# MTB-v1_2_0.net
KiCad netlist of a schematic drawn in EAGLE
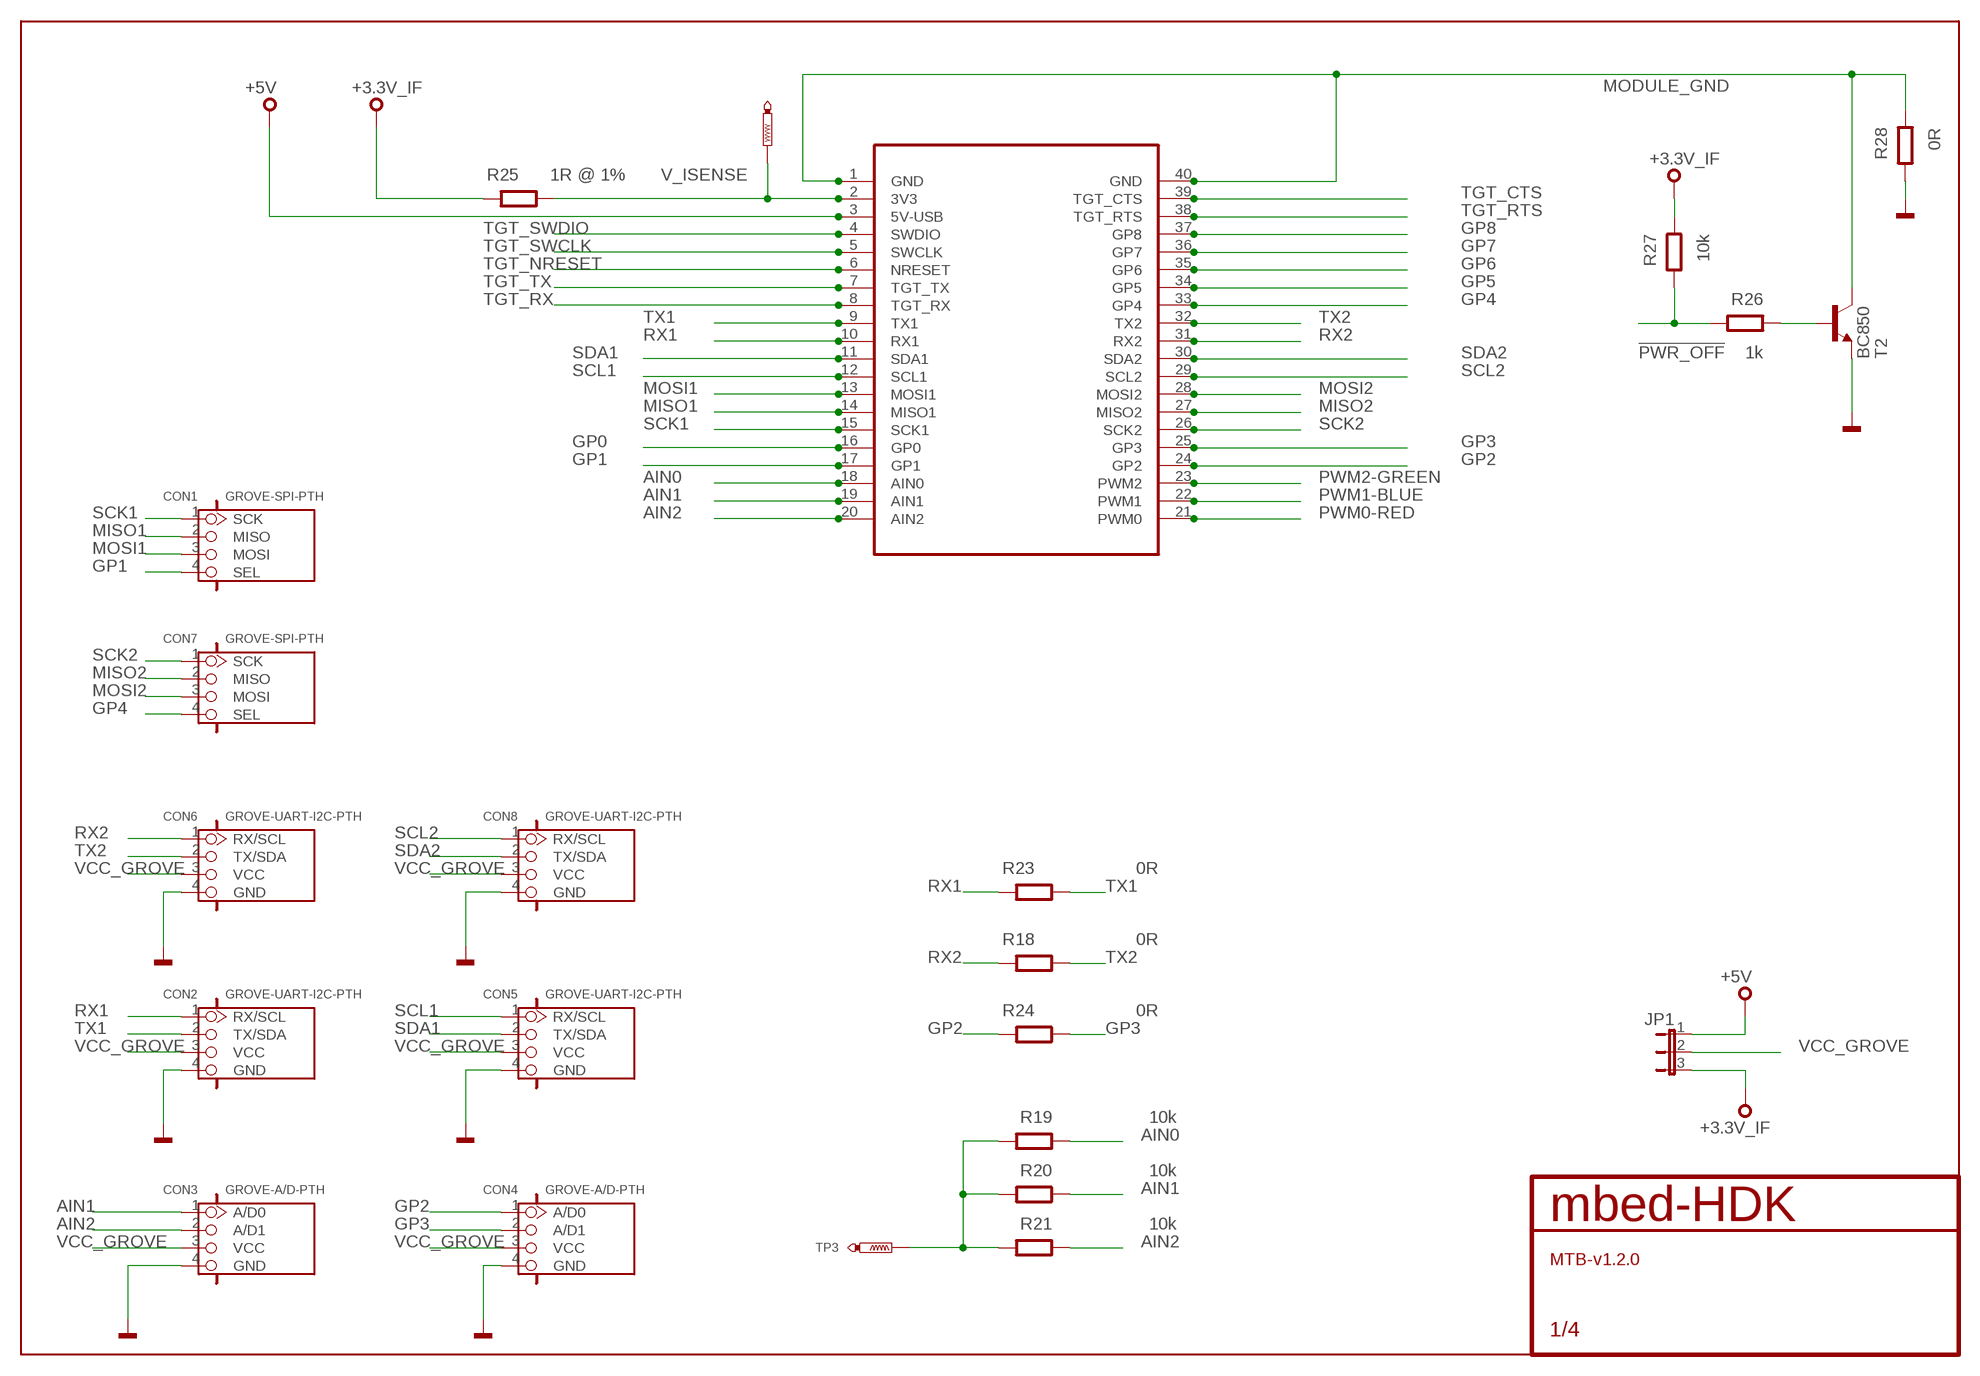
[diagram p0: schematic, sheet 1]
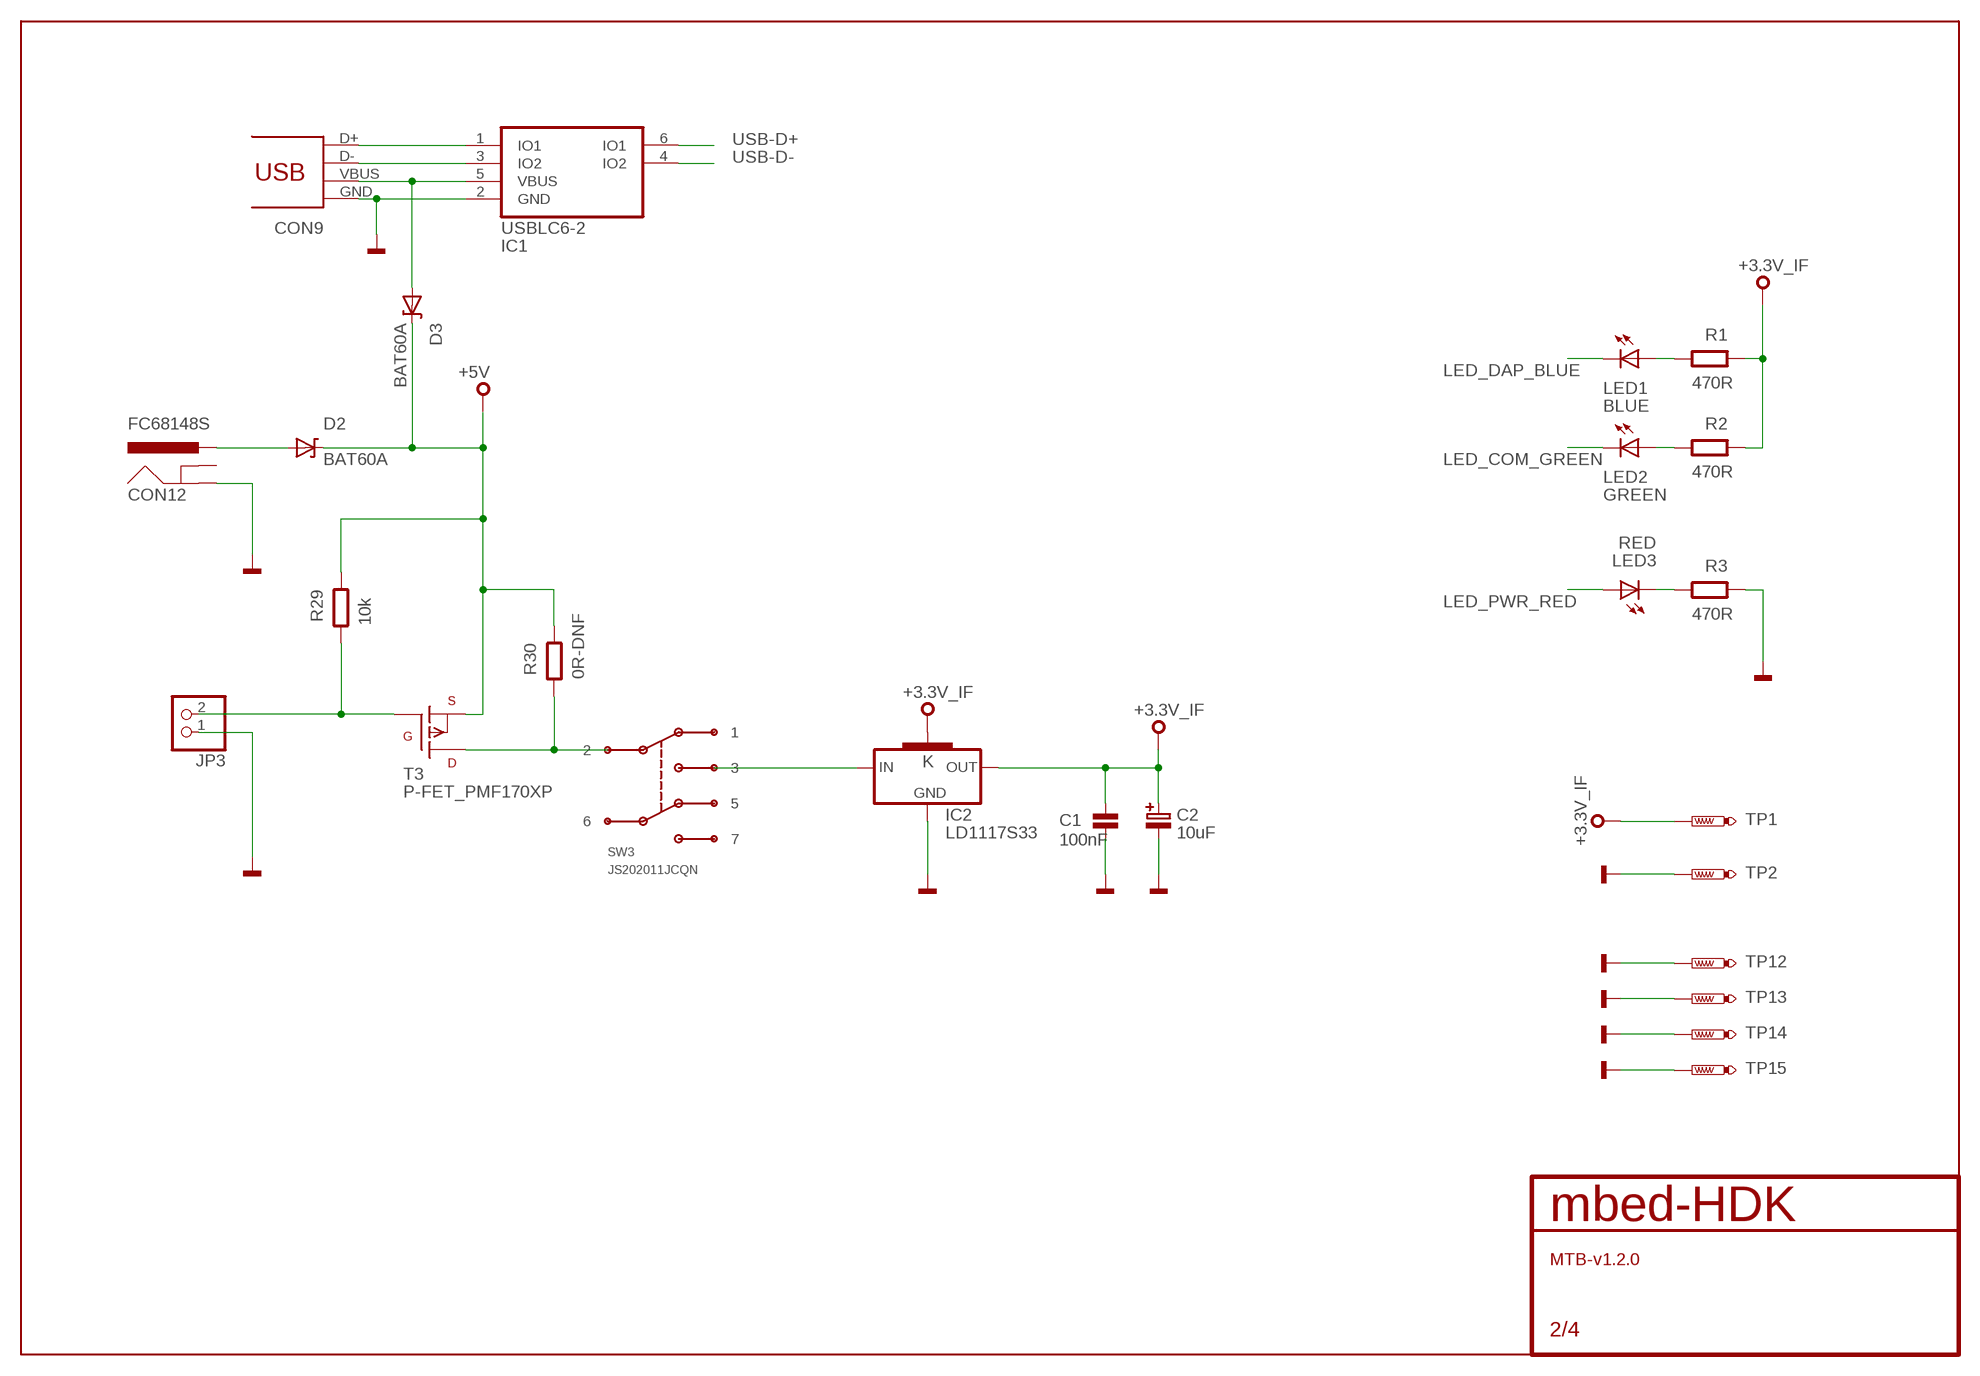
[diagram p1: schematic, sheet 2]
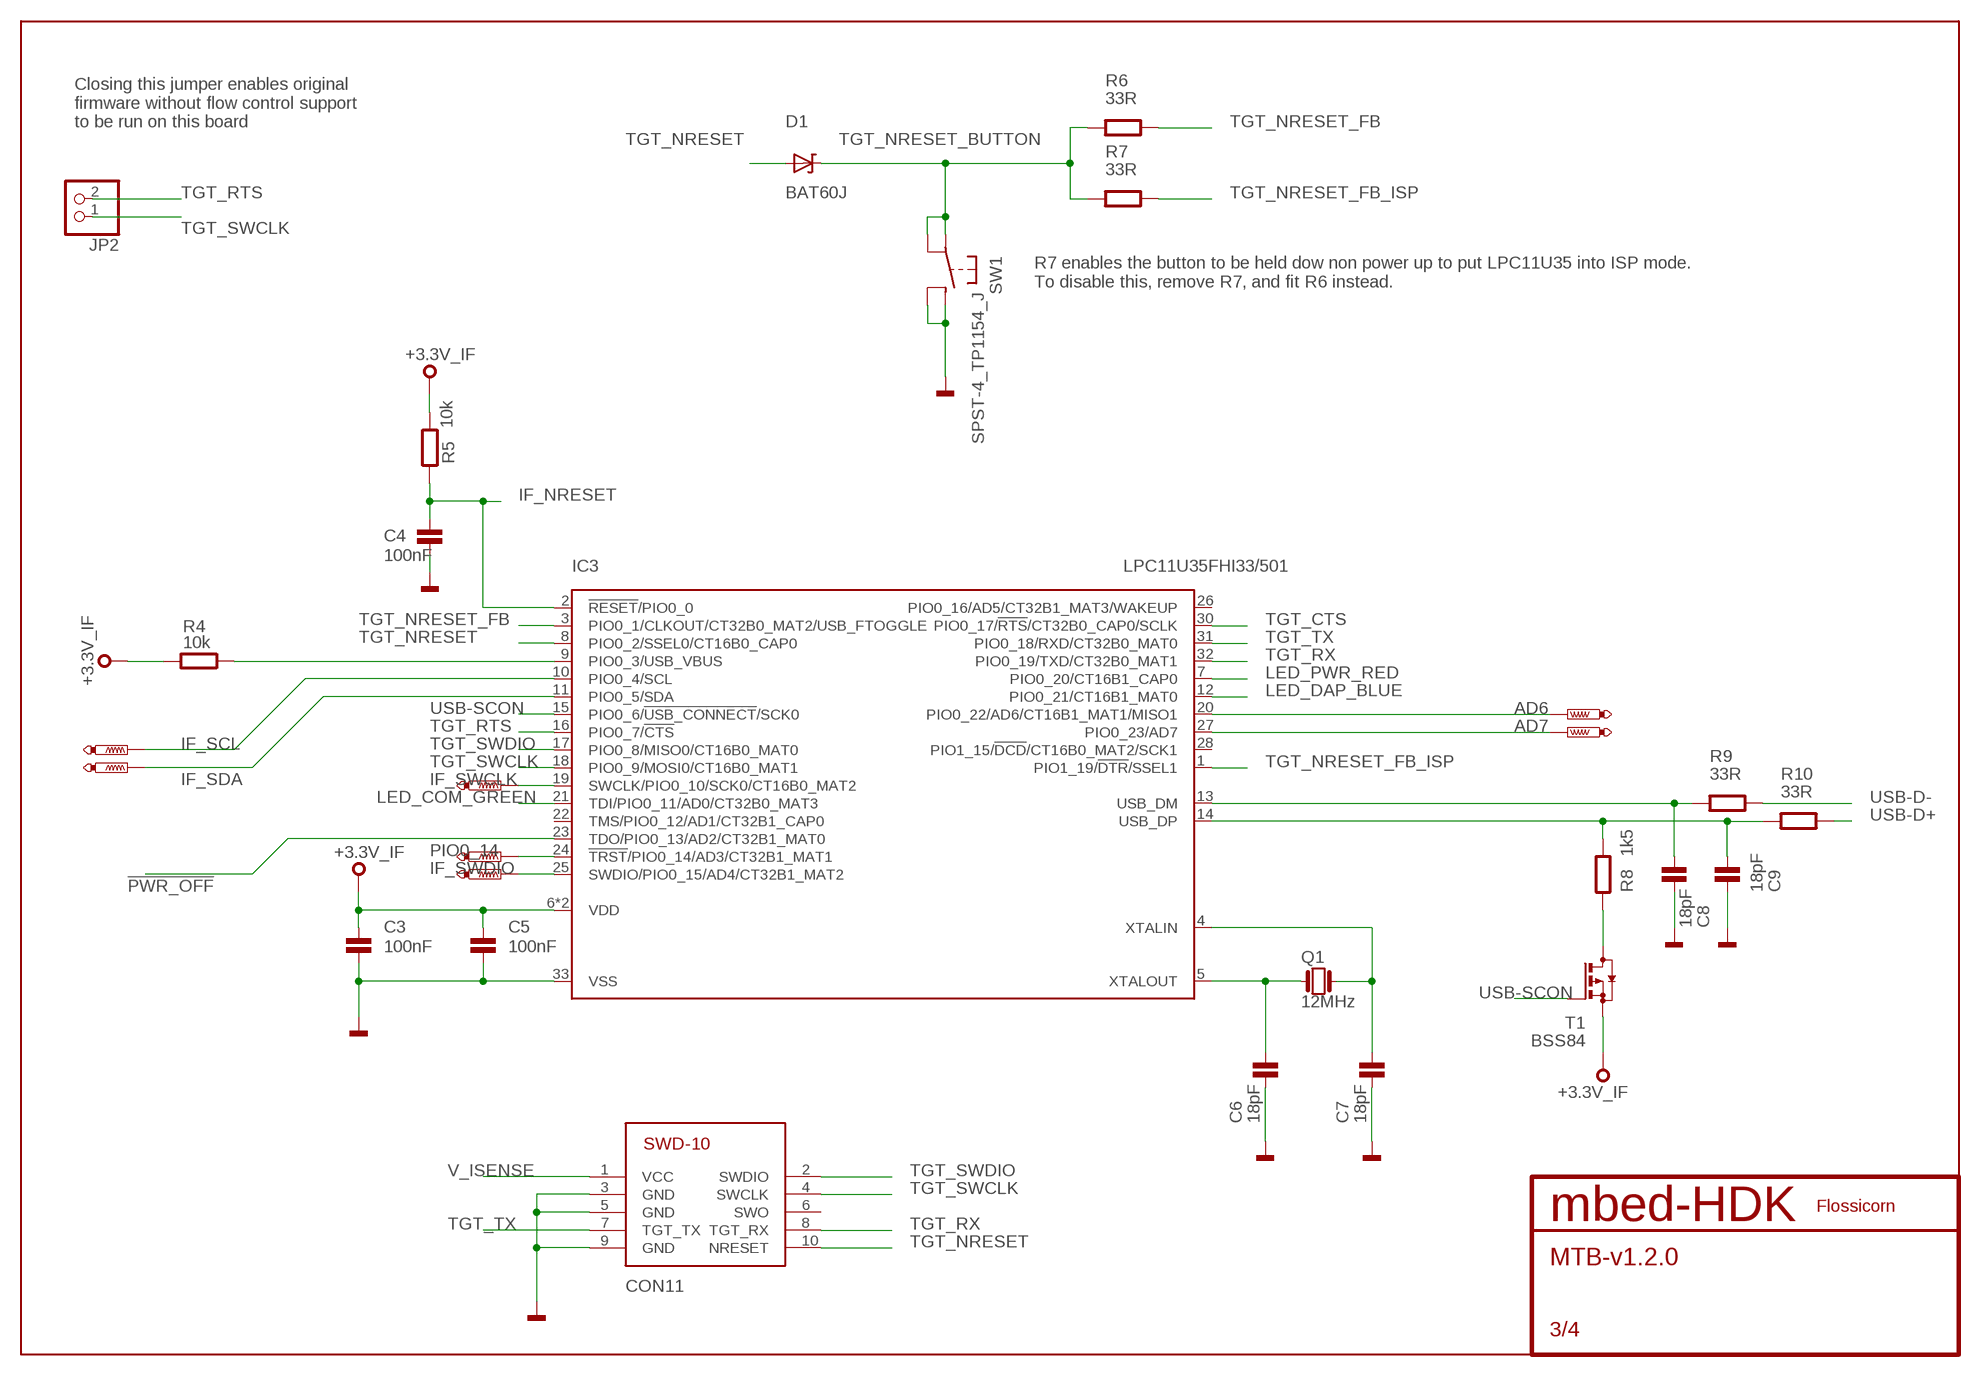
[diagram p2: schematic, sheet 3]
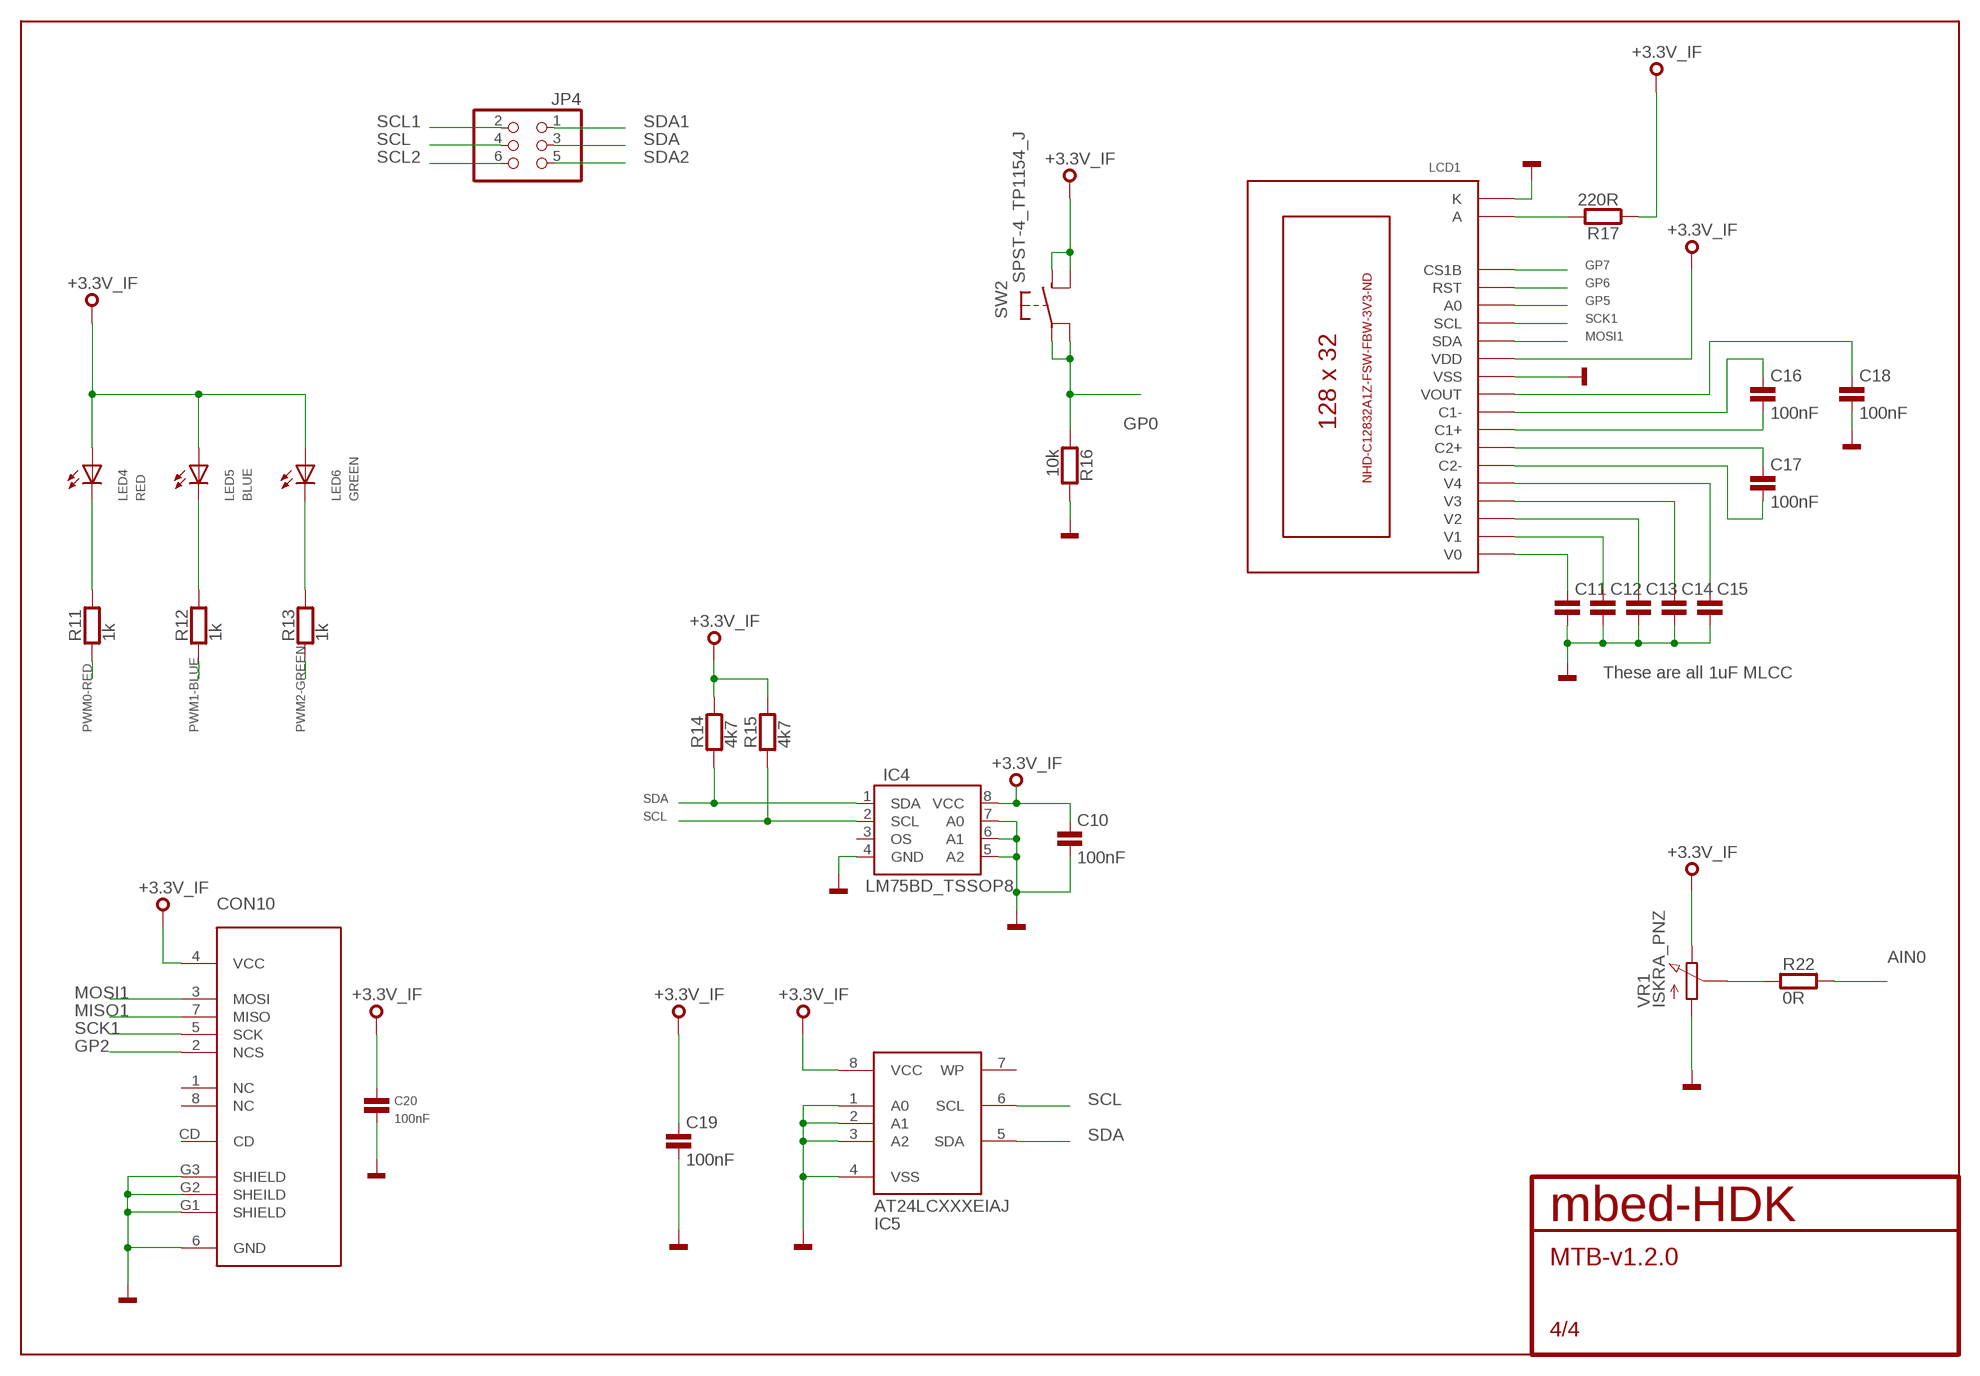
[diagram p3: schematic, sheet 4]

(export (version "E")
  (design (tool "Eeschema 10.0.6"))
  (components
    (comp (ref "C10")
      (value "100nF")
      (footprint "eagle-import:0603")
      (libsource (lib "eagle-import") (part "mbed-rlcq_C0603"))
    )
    (comp (ref "C11")
      (value "100nF")
      (footprint "eagle-import:0603")
      (libsource (lib "eagle-import") (part "mbed-rlcq_C0603"))
    )
    (comp (ref "C12")
      (value "100nF")
      (footprint "eagle-import:0603")
      (libsource (lib "eagle-import") (part "mbed-rlcq_C0603"))
    )
    (comp (ref "C13")
      (value "100nF")
      (footprint "eagle-import:0603")
      (libsource (lib "eagle-import") (part "mbed-rlcq_C0603"))
    )
    (comp (ref "C14")
      (value "100nF")
      (footprint "eagle-import:0603")
      (libsource (lib "eagle-import") (part "mbed-rlcq_C0603"))
    )
    (comp (ref "C15")
      (value "100nF")
      (footprint "eagle-import:0603")
      (libsource (lib "eagle-import") (part "mbed-rlcq_C0603"))
    )
    (comp (ref "C16")
      (value "100nF")
      (footprint "eagle-import:0603")
      (libsource (lib "eagle-import") (part "mbed-rlcq_C0603"))
    )
    (comp (ref "C17")
      (value "100nF")
      (footprint "eagle-import:0603")
      (libsource (lib "eagle-import") (part "mbed-rlcq_C0603"))
    )
    (comp (ref "C18")
      (value "100nF")
      (footprint "eagle-import:0603")
      (libsource (lib "eagle-import") (part "mbed-rlcq_C0603"))
    )
    (comp (ref "C19")
      (value "100nF")
      (footprint "eagle-import:0603")
      (libsource (lib "eagle-import") (part "mbed-rlcq_C0603"))
    )
    (comp (ref "C20")
      (value "100nF")
      (footprint "eagle-import:0603")
      (libsource (lib "eagle-import") (part "C0603"))
    )
    (comp (ref "CON10")
      (value "MICRO-SD")
      (footprint "eagle-import:AMPHENOL-101-00660-68-6")
      (libsource (lib "eagle-import") (part "MICRO-SD"))
    )
    (comp (ref "IC4")
      (value "LM75BD_TSSOP8")
      (footprint "eagle-import:TSSOP8")
      (libsource (lib "eagle-import") (part "LM75BD_TSSOP8"))
    )
    (comp (ref "IC5")
      (value "AT24LCXXXEIAJ")
      (footprint "eagle-import:SO08-EIAJ")
      (libsource (lib "eagle-import") (part "AT24LCXXXEIAJ"))
    )
    (comp (ref "JP4")
      (value "PINHD-2X3")
      (footprint "eagle-import:2X03")
      (libsource (lib "eagle-import") (part "PINHD-2X3"))
    )
    (comp (ref "LCD1")
      (value "C12832A1Z")
      (footprint "eagle-import:C12832A1Z")
      (libsource (lib "eagle-import") (part "C12832A1Z"))
    )
    (comp (ref "LED4")
      (value "RED")
      (footprint "eagle-import:CHIPLED_0603")
      (libsource (lib "eagle-import") (part "LED0603"))
    )
    (comp (ref "LED5")
      (value "BLUE")
      (footprint "eagle-import:CHIPLED_0603")
      (libsource (lib "eagle-import") (part "LED0603"))
    )
    (comp (ref "LED6")
      (value "GREEN")
      (footprint "eagle-import:CHIPLED_0603")
      (libsource (lib "eagle-import") (part "LED0603"))
    )
    (comp (ref "R11")
      (value "1k")
      (footprint "eagle-import:0603")
      (libsource (lib "eagle-import") (part "mbed-rlcq_R0603"))
    )
    (comp (ref "R12")
      (value "1k")
      (footprint "eagle-import:0603")
      (libsource (lib "eagle-import") (part "mbed-rlcq_R0603"))
    )
    (comp (ref "R13")
      (value "1k")
      (footprint "eagle-import:0603")
      (libsource (lib "eagle-import") (part "mbed-rlcq_R0603"))
    )
    (comp (ref "R14")
      (value "4k7")
      (footprint "eagle-import:0603")
      (libsource (lib "eagle-import") (part "mbed-rlcq_R0603"))
    )
    (comp (ref "R15")
      (value "4k7")
      (footprint "eagle-import:0603")
      (libsource (lib "eagle-import") (part "mbed-rlcq_R0603"))
    )
    (comp (ref "R16")
      (value "10k")
      (footprint "eagle-import:0603")
      (libsource (lib "eagle-import") (part "mbed-rlcq_R0603"))
    )
    (comp (ref "R17")
      (value "220R")
      (footprint "eagle-import:0603")
      (libsource (lib "eagle-import") (part "mbed-rlcq_R0603"))
    )
    (comp (ref "R22")
      (value "0R")
      (footprint "eagle-import:0603")
      (libsource (lib "eagle-import") (part "mbed-rlcq_R0603"))
    )
    (comp (ref "SW2")
      (value "SPST-4_TP1154_J")
      (footprint "eagle-import:TP-1154X")
      (libsource (lib "eagle-import") (part "SPST-4_TP1154_J"))
    )
    (comp (ref "VR1")
      (value "ISKRA_PNZ")
      (footprint "eagle-import:CA14V")
      (libsource (lib "eagle-import") (part "ISKRA_PNZ"))
    )
    (comp (ref "C1")
      (value "100nF")
      (footprint "eagle-import:0603")
      (libsource (lib "eagle-import") (part "C0603"))
    )
    (comp (ref "C2")
      (value "10uF")
      (footprint "eagle-import:SMC_B")
      (libsource (lib "eagle-import") (part "C-POLB"))
    )
    (comp (ref "CON9")
      (value "USB_MICROB")
      (footprint "eagle-import:MOLEX-47364-0001")
      (libsource (lib "eagle-import") (part "USB_MICROB"))
    )
    (comp (ref "CON12")
      (value "FC68148S")
      (footprint "eagle-import:FC68148S")
      (libsource (lib "eagle-import") (part "FC68148S"))
    )
    (comp (ref "D2")
      (value "BAT60A")
      (footprint "eagle-import:SOD323")
      (fields (field (name "MF") "Infineon"))
      (libsource (lib "eagle-import") (part "mbed-HDK-Transistor_BAT60A"))
    )
    (comp (ref "D3")
      (value "BAT60A")
      (footprint "eagle-import:SOD323")
      (fields (field (name "MF") "Infineon"))
      (libsource (lib "eagle-import") (part "mbed-HDK-Transistor_BAT60A"))
    )
    (comp (ref "IC1")
      (value "USBLC6-2SC6")
      (footprint "eagle-import:SOT23-6L")
      (libsource (lib "eagle-import") (part "USBLC6-2SC6"))
    )
    (comp (ref "IC2")
      (value "LD1117S33")
      (footprint "eagle-import:SOT223")
      (libsource (lib "eagle-import") (part "LD1117S33"))
    )
    (comp (ref "JP3")
      (value "PINHD-1X2")
      (footprint "eagle-import:1X02")
      (libsource (lib "eagle-import") (part "PINHD-1X2"))
    )
    (comp (ref "LED1")
      (value "BLUE")
      (footprint "eagle-import:CHIPLED_0603")
      (libsource (lib "eagle-import") (part "LED0603"))
    )
    (comp (ref "LED2")
      (value "GREEN")
      (footprint "eagle-import:CHIPLED_0603")
      (libsource (lib "eagle-import") (part "LED0603"))
    )
    (comp (ref "LED3")
      (value "RED")
      (footprint "eagle-import:CHIPLED_0603")
      (libsource (lib "eagle-import") (part "LED0603"))
    )
    (comp (ref "R1")
      (value "470R")
      (footprint "eagle-import:0603@1")
      (libsource (lib "eagle-import") (part "R0603"))
    )
    (comp (ref "R2")
      (value "470R")
      (footprint "eagle-import:0603@1")
      (libsource (lib "eagle-import") (part "R0603"))
    )
    (comp (ref "R3")
      (value "470R")
      (footprint "eagle-import:0603@1")
      (libsource (lib "eagle-import") (part "R0603"))
    )
    (comp (ref "R29")
      (value "10k")
      (footprint "eagle-import:0603@1")
      (libsource (lib "eagle-import") (part "R0603"))
    )
    (comp (ref "R30")
      (value "0R-DNF")
      (footprint "eagle-import:0603@1")
      (libsource (lib "eagle-import") (part "R0603"))
    )
    (comp (ref "SW3")
      (value "JS202011JCQN")
      (footprint "eagle-import:JS202011JCQN")
      (fields (field (name "MF") "C&K Components"))
      (libsource (lib "eagle-import") (part "JS202011JCQN"))
    )
    (comp (ref "T3")
      (value "P-FET_PMF170XP")
      (footprint "eagle-import:SOT23-BEC")
      (libsource (lib "eagle-import") (part "P-FET_PMF170XP"))
    )
    (comp (ref "TP1")
      (value "TEST-POINT-50R-PTH")
      (footprint "eagle-import:TP50-PTH")
      (libsource (lib "eagle-import") (part "TEST-POINT-50R-PTH"))
    )
    (comp (ref "TP2")
      (value "TEST-POINT-50R-PTH")
      (footprint "eagle-import:TP50-PTH")
      (libsource (lib "eagle-import") (part "TEST-POINT-50R-PTH"))
    )
    (comp (ref "TP12")
      (value "TEST-POINT-50R-PTH")
      (footprint "eagle-import:TP50-PTH")
      (libsource (lib "eagle-import") (part "TEST-POINT-50R-PTH"))
    )
    (comp (ref "TP13")
      (value "TEST-POINT-50R-PTH")
      (footprint "eagle-import:TP50-PTH")
      (libsource (lib "eagle-import") (part "TEST-POINT-50R-PTH"))
    )
    (comp (ref "TP14")
      (value "TEST-POINT-50R-PTH")
      (footprint "eagle-import:TP50-PTH")
      (libsource (lib "eagle-import") (part "TEST-POINT-50R-PTH"))
    )
    (comp (ref "TP15")
      (value "TEST-POINT-50R-PTH")
      (footprint "eagle-import:TP50-PTH")
      (libsource (lib "eagle-import") (part "TEST-POINT-50R-PTH"))
    )
    (comp (ref "CON1")
      (value "GROVE-SPI-PTH")
      (footprint "eagle-import:HW4-2.0")
      (libsource (lib "eagle-import") (part "GROVE-SPI-PTH"))
    )
    (comp (ref "CON2")
      (value "GROVE-UART-I2C-PTH")
      (footprint "eagle-import:HW4-2.0")
      (libsource (lib "eagle-import") (part "GROVE-UART-I2C-PTH"))
    )
    (comp (ref "CON3")
      (value "GROVE-A/D-PTH")
      (footprint "eagle-import:HW4-2.0")
      (libsource (lib "eagle-import") (part "GROVE-A/D-PTH"))
    )
    (comp (ref "CON4")
      (value "GROVE-A/D-PTH")
      (footprint "eagle-import:HW4-2.0")
      (libsource (lib "eagle-import") (part "GROVE-A/D-PTH"))
    )
    (comp (ref "CON5")
      (value "GROVE-UART-I2C-PTH")
      (footprint "eagle-import:HW4-2.0")
      (libsource (lib "eagle-import") (part "GROVE-UART-I2C-PTH"))
    )
    (comp (ref "CON6")
      (value "GROVE-UART-I2C-PTH")
      (footprint "eagle-import:HW4-2.0")
      (libsource (lib "eagle-import") (part "GROVE-UART-I2C-PTH"))
    )
    (comp (ref "CON7")
      (value "GROVE-SPI-PTH")
      (footprint "eagle-import:HW4-2.0")
      (libsource (lib "eagle-import") (part "GROVE-SPI-PTH"))
    )
    (comp (ref "CON8")
      (value "GROVE-UART-I2C-PTH")
      (footprint "eagle-import:HW4-2.0")
      (libsource (lib "eagle-import") (part "GROVE-UART-I2C-PTH"))
    )
    (comp (ref "JP1")
      (value "JP2E")
      (footprint "eagle-import:JP2")
      (libsource (lib "eagle-import") (part "JP2E"))
    )
    (comp (ref "R18")
      (value "0R")
      (footprint "eagle-import:0603@1")
      (libsource (lib "eagle-import") (part "R0603"))
    )
    (comp (ref "R19")
      (value "10k")
      (footprint "eagle-import:0603@1")
      (libsource (lib "eagle-import") (part "R0603"))
    )
    (comp (ref "R20")
      (value "10k")
      (footprint "eagle-import:0603@1")
      (libsource (lib "eagle-import") (part "R0603"))
    )
    (comp (ref "R21")
      (value "10k")
      (footprint "eagle-import:0603@1")
      (libsource (lib "eagle-import") (part "R0603"))
    )
    (comp (ref "R23")
      (value "0R")
      (footprint "eagle-import:0603@1")
      (libsource (lib "eagle-import") (part "R0603"))
    )
    (comp (ref "R24")
      (value "0R")
      (footprint "eagle-import:0603@1")
      (libsource (lib "eagle-import") (part "R0603"))
    )
    (comp (ref "R25")
      (value "1R @ 1%")
      (footprint "eagle-import:0603@1")
      (libsource (lib "eagle-import") (part "R0603"))
    )
    (comp (ref "R26")
      (value "1k")
      (footprint "eagle-import:0603@1")
      (libsource (lib "eagle-import") (part "R0603"))
    )
    (comp (ref "R27")
      (value "10k")
      (footprint "eagle-import:0603@1")
      (libsource (lib "eagle-import") (part "R0603"))
    )
    (comp (ref "R28")
      (value "0R")
      (footprint "eagle-import:0603@1")
      (libsource (lib "eagle-import") (part "R0603"))
    )
    (comp (ref "SKT1")
      (value "MODULE_SOCKET")
      (footprint "eagle-import:MODULE_SOCKET")
      (libsource (lib "eagle-import") (part "MODULE_SOCKET"))
    )
    (comp (ref "T2")
      (value "BC850")
      (footprint "eagle-import:SOT23")
      (libsource (lib "eagle-import") (part "BC850"))
    )
    (comp (ref "TP3")
      (value "TEST-POINT-50R-PTH")
      (footprint "eagle-import:TP50-PTH")
      (libsource (lib "eagle-import") (part "TEST-POINT-50R-PTH"))
    )
    (comp (ref "TP8")
      (value "PTR1TP07R")
      (footprint "eagle-import:TP07R")
      (libsource (lib "eagle-import") (part "PTR1TP07R"))
    )
    (comp (ref "C3")
      (value "100nF")
      (footprint "eagle-import:0603")
      (libsource (lib "eagle-import") (part "C0603"))
    )
    (comp (ref "C4")
      (value "100nF")
      (footprint "eagle-import:0603")
      (libsource (lib "eagle-import") (part "C0603"))
    )
    (comp (ref "C5")
      (value "100nF")
      (footprint "eagle-import:0603")
      (libsource (lib "eagle-import") (part "C0603"))
    )
    (comp (ref "C6")
      (value "18pF")
      (footprint "eagle-import:0603")
      (libsource (lib "eagle-import") (part "C0603"))
    )
    (comp (ref "C7")
      (value "18pF")
      (footprint "eagle-import:0603")
      (libsource (lib "eagle-import") (part "C0603"))
    )
    (comp (ref "C8")
      (value "18pF")
      (footprint "eagle-import:0603")
      (libsource (lib "eagle-import") (part "C0603"))
    )
    (comp (ref "C9")
      (value "18pF")
      (footprint "eagle-import:0603")
      (libsource (lib "eagle-import") (part "C0603"))
    )
    (comp (ref "CON11")
      (value "SWD-10/TC2050_SMD")
      (footprint "eagle-import:FTSH-105-02")
      (libsource (lib "eagle-import") (part "SWD-10/TC2050_SMD"))
    )
    (comp (ref "D1")
      (value "BAT60J")
      (footprint "eagle-import:BAT60A")
      (libsource (lib "eagle-import") (part "BAT60A"))
    )
    (comp (ref "IC3")
      (value "LPC11U35FHI33/501")
      (footprint "eagle-import:SOT617-3")
      (libsource (lib "eagle-import") (part "LPC11U35FHI33/501"))
    )
    (comp (ref "JP2")
      (value "PINHD-1X2")
      (footprint "eagle-import:1X02")
      (libsource (lib "eagle-import") (part "PINHD-1X2"))
    )
    (comp (ref "Q1")
      (value "12MHz")
      (footprint "eagle-import:3.2X.2.5")
      (libsource (lib "eagle-import") (part "Q_3.2X2.5"))
    )
    (comp (ref "R4")
      (value "10k")
      (footprint "eagle-import:0603@1")
      (libsource (lib "eagle-import") (part "R0603"))
    )
    (comp (ref "R5")
      (value "10k")
      (footprint "eagle-import:0603@1")
      (libsource (lib "eagle-import") (part "R0603"))
    )
    (comp (ref "R6")
      (value "33R")
      (footprint "eagle-import:0603@1")
      (libsource (lib "eagle-import") (part "R0603"))
    )
    (comp (ref "R7")
      (value "33R")
      (footprint "eagle-import:0603@1")
      (libsource (lib "eagle-import") (part "R0603"))
    )
    (comp (ref "R8")
      (value "1k5")
      (footprint "eagle-import:0603@1")
      (libsource (lib "eagle-import") (part "R0603"))
    )
    (comp (ref "R9")
      (value "33R")
      (footprint "eagle-import:0603@1")
      (libsource (lib "eagle-import") (part "R0603"))
    )
    (comp (ref "R10")
      (value "33R")
      (footprint "eagle-import:0603@1")
      (libsource (lib "eagle-import") (part "R0603"))
    )
    (comp (ref "SS1")
      (value "FLOSSICORN0.5")
      (footprint "eagle-import:FLOSSICORN-0.5")
      (libsource (lib "eagle-import") (part "FLOSSICORN0.5"))
    )
    (comp (ref "SW1")
      (value "SPST-4_TP1154_J")
      (footprint "eagle-import:TP-1154X")
      (libsource (lib "eagle-import") (part "SPST-4_TP1154_J"))
    )
    (comp (ref "T1")
      (value "BSS84")
      (footprint "eagle-import:SOT23")
      (libsource (lib "eagle-import") (part "BSS84"))
    )
    (comp (ref "TP4")
      (value "PTR1TP07R")
      (footprint "eagle-import:TP07R")
      (libsource (lib "eagle-import") (part "PTR1TP07R"))
    )
    (comp (ref "TP5")
      (value "PTR1TP07R")
      (footprint "eagle-import:TP07R")
      (libsource (lib "eagle-import") (part "PTR1TP07R"))
    )
    (comp (ref "TP6")
      (value "PTR1TP07R")
      (footprint "eagle-import:TP07R")
      (libsource (lib "eagle-import") (part "PTR1TP07R"))
    )
    (comp (ref "TP7")
      (value "PTR1TP07R")
      (footprint "eagle-import:TP07R")
      (libsource (lib "eagle-import") (part "PTR1TP07R"))
    )
    (comp (ref "TP9")
      (value "PTR1TP07R")
      (footprint "eagle-import:TP07R")
      (libsource (lib "eagle-import") (part "PTR1TP07R"))
    )
    (comp (ref "TP10")
      (value "PTR1TP07R")
      (footprint "eagle-import:TP07R")
      (libsource (lib "eagle-import") (part "PTR1TP07R"))
    )
    (comp (ref "TP11")
      (value "PTR1TP07R")
      (footprint "eagle-import:TP07R")
      (libsource (lib "eagle-import") (part "PTR1TP07R"))
    )
  )
  (nets
    (net (code "1") (name "+3.3V_IF") (class "Default")
      (node (ref "C1") (pin "1") (pinfunction "P$1_1") (pintype "passive"))
      (node (ref "C10") (pin "1") (pinfunction "P$1_1") (pintype "passive"))
      (node (ref "C19") (pin "1") (pinfunction "P$1_1") (pintype "passive"))
      (node (ref "C2") (pin "+") (pinfunction "+_+") (pintype "passive"))
      (node (ref "C20") (pin "1") (pinfunction "P$1_1") (pintype "passive"))
      (node (ref "C3") (pin "1") (pinfunction "P$1_1") (pintype "passive"))
      (node (ref "C5") (pin "1") (pinfunction "P$1_1") (pintype "passive"))
      (node (ref "CON10") (pin "4") (pinfunction "VCC_4") (pintype "bidirectional"))
      (node (ref "IC2") (pin "2") (pinfunction "OUT_2") (pintype "passive"))
      (node (ref "IC2") (pin "4") (pinfunction "K_4") (pintype "passive"))
      (node (ref "IC3") (pin "29") (pinfunction "VDD_29") (pintype "passive"))
      (node (ref "IC3") (pin "6") (pinfunction "VDD_6") (pintype "passive"))
      (node (ref "IC4") (pin "8") (pinfunction "VCC_8") (pintype "bidirectional"))
      (node (ref "IC5") (pin "8") (pinfunction "VCC_8") (pintype "power_in"))
      (node (ref "JP1") (pin "3") (pinfunction "3_3") (pintype "passive"))
      (node (ref "LCD1") (pin "P$12") (pinfunction "VDD_P$12") (pintype "bidirectional"))
      (node (ref "LED4") (pin "A") (pinfunction "A_A") (pintype "passive"))
      (node (ref "LED5") (pin "A") (pinfunction "A_A") (pintype "passive"))
      (node (ref "LED6") (pin "A") (pinfunction "A_A") (pintype "passive"))
      (node (ref "R1") (pin "1") (pinfunction "P$1_1") (pintype "passive"))
      (node (ref "R14") (pin "2") (pinfunction "P$2_2") (pintype "passive"))
      (node (ref "R15") (pin "2") (pinfunction "P$2_2") (pintype "passive"))
      (node (ref "R17") (pin "1") (pinfunction "P$1_1") (pintype "passive"))
      (node (ref "R2") (pin "1") (pinfunction "P$1_1") (pintype "passive"))
      (node (ref "R25") (pin "2") (pinfunction "P$2_2") (pintype "passive"))
      (node (ref "R27") (pin "1") (pinfunction "P$1_1") (pintype "passive"))
      (node (ref "R4") (pin "2") (pinfunction "P$2_2") (pintype "passive"))
      (node (ref "R5") (pin "2") (pinfunction "P$2_2") (pintype "passive"))
      (node (ref "SW2") (pin "B1") (pinfunction "B1_B1") (pintype "passive"))
      (node (ref "SW2") (pin "B2") (pinfunction "B2_B2") (pintype "passive"))
      (node (ref "T1") (pin "2") (pinfunction "S_2") (pintype "passive"))
      (node (ref "TP1") (pin "TP") (pinfunction "TP_TP") (pintype "input"))
      (node (ref "VR1") (pin "P$3") (pinfunction "E_P$3") (pintype "passive"))
    )
    (net (code "2") (name "+5V") (class "Default")
      (node (ref "D2") (pin "K") (pinfunction "K_K") (pintype "passive"))
      (node (ref "D3") (pin "K") (pinfunction "K_K") (pintype "passive"))
      (node (ref "JP1") (pin "1") (pinfunction "1_1") (pintype "passive"))
      (node (ref "R29") (pin "1") (pinfunction "P$1_1") (pintype "passive"))
      (node (ref "R30") (pin "1") (pinfunction "P$1_1") (pintype "passive"))
      (node (ref "SKT1") (pin "3") (pinfunction "5V-USB_3") (pintype "bidirectional"))
      (node (ref "SKT1") (pin "P$43") (pinfunction "P$43_P$43") (pintype "bidirectional"))
      (node (ref "T3") (pin "E") (pinfunction "S_E") (pintype "passive"))
    )
    (net (code "3") (name "AD6") (class "Default")
      (node (ref "IC3") (pin "20") (pinfunction "PIO0_22/AD6/CT16B1_MAT1/MISO1_20") (pintype "bidirectional"))
      (node (ref "TP7") (pin "TP") (pinfunction "TP_TP") (pintype "input"))
    )
    (net (code "4") (name "AD7") (class "Default")
      (node (ref "IC3") (pin "27") (pinfunction "PIO0_23/AD7_27") (pintype "bidirectional"))
      (node (ref "TP6") (pin "TP") (pinfunction "TP_TP") (pintype "input"))
    )
    (net (code "5") (name "AIN0") (class "Default")
      (node (ref "R19") (pin "1") (pinfunction "P$1_1") (pintype "passive"))
      (node (ref "R22") (pin "2") (pinfunction "P$2_2") (pintype "passive"))
      (node (ref "SKT1") (pin "18") (pinfunction "AIN0_18") (pintype "bidirectional"))
      (node (ref "SKT1") (pin "P$58") (pinfunction "P$58_P$58") (pintype "bidirectional"))
    )
    (net (code "6") (name "AIN1") (class "Default")
      (node (ref "CON3") (pin "1") (pinfunction "A/D0_1") (pintype "bidirectional"))
      (node (ref "R20") (pin "1") (pinfunction "P$1_1") (pintype "passive"))
      (node (ref "SKT1") (pin "19") (pinfunction "AIN1_19") (pintype "bidirectional"))
      (node (ref "SKT1") (pin "P$59") (pinfunction "P$59_P$59") (pintype "bidirectional"))
    )
    (net (code "7") (name "AIN2") (class "Default")
      (node (ref "CON3") (pin "2") (pinfunction "A/D1_2") (pintype "bidirectional"))
      (node (ref "R21") (pin "1") (pinfunction "P$1_1") (pintype "passive"))
      (node (ref "SKT1") (pin "20") (pinfunction "AIN2_20") (pintype "bidirectional"))
      (node (ref "SKT1") (pin "P$60") (pinfunction "P$60_P$60") (pintype "bidirectional"))
    )
    (net (code "8") (name "GND") (class "Default")
      (node (ref "C1") (pin "2") (pinfunction "P$2_2") (pintype "passive"))
      (node (ref "C10") (pin "2") (pinfunction "P$2_2") (pintype "passive"))
      (node (ref "C11") (pin "2") (pinfunction "P$2_2") (pintype "passive"))
      (node (ref "C12") (pin "2") (pinfunction "P$2_2") (pintype "passive"))
      (node (ref "C13") (pin "2") (pinfunction "P$2_2") (pintype "passive"))
      (node (ref "C14") (pin "2") (pinfunction "P$2_2") (pintype "passive"))
      (node (ref "C15") (pin "2") (pinfunction "P$2_2") (pintype "passive"))
      (node (ref "C18") (pin "2") (pinfunction "P$2_2") (pintype "passive"))
      (node (ref "C19") (pin "2") (pinfunction "P$2_2") (pintype "passive"))
      (node (ref "C2") (pin "-") (pinfunction "-_-") (pintype "passive"))
      (node (ref "C20") (pin "2") (pinfunction "P$2_2") (pintype "passive"))
      (node (ref "C3") (pin "2") (pinfunction "P$2_2") (pintype "passive"))
      (node (ref "C4") (pin "2") (pinfunction "P$2_2") (pintype "passive"))
      (node (ref "C5") (pin "2") (pinfunction "P$2_2") (pintype "passive"))
      (node (ref "C6") (pin "2") (pinfunction "P$2_2") (pintype "passive"))
      (node (ref "C7") (pin "2") (pinfunction "P$2_2") (pintype "passive"))
      (node (ref "C8") (pin "2") (pinfunction "P$2_2") (pintype "passive"))
      (node (ref "C9") (pin "2") (pinfunction "P$2_2") (pintype "passive"))
      (node (ref "CON10") (pin "6") (pinfunction "GND_6") (pintype "bidirectional"))
      (node (ref "CON10") (pin "G1") (pinfunction "SHIELD_G1") (pintype "bidirectional"))
      (node (ref "CON10") (pin "G2") (pinfunction "SHEILD_G2") (pintype "bidirectional"))
      (node (ref "CON10") (pin "G3") (pinfunction "SHIELD_G3") (pintype "bidirectional"))
      (node (ref "CON11") (pin "3") (pinfunction "GND_3") (pintype "bidirectional"))
      (node (ref "CON11") (pin "5") (pinfunction "GND_5") (pintype "bidirectional"))
      (node (ref "CON11") (pin "9") (pinfunction "GND_9") (pintype "bidirectional"))
      (node (ref "CON12") (pin "3") (pinfunction "GND_3") (pintype "bidirectional"))
      (node (ref "CON2") (pin "4") (pinfunction "GND_4") (pintype "bidirectional"))
      (node (ref "CON3") (pin "4") (pinfunction "GND_4") (pintype "bidirectional"))
      (node (ref "CON4") (pin "4") (pinfunction "GND_4") (pintype "bidirectional"))
      (node (ref "CON5") (pin "4") (pinfunction "GND_4") (pintype "bidirectional"))
      (node (ref "CON6") (pin "4") (pinfunction "GND_4") (pintype "bidirectional"))
      (node (ref "CON8") (pin "4") (pinfunction "GND_4") (pintype "bidirectional"))
      (node (ref "CON9") (pin "GND") (pinfunction "GND_GND") (pintype "bidirectional"))
      (node (ref "IC1") (pin "2") (pinfunction "GND_2") (pintype "bidirectional"))
      (node (ref "IC2") (pin "1") (pinfunction "GND_1") (pintype "input"))
      (node (ref "IC3") (pin "33") (pinfunction "VSS_33") (pintype "passive"))
      (node (ref "IC4") (pin "4") (pinfunction "GND_4") (pintype "bidirectional"))
      (node (ref "IC4") (pin "5") (pinfunction "A2_5") (pintype "bidirectional"))
      (node (ref "IC4") (pin "6") (pinfunction "A1_6") (pintype "bidirectional"))
      (node (ref "IC4") (pin "7") (pinfunction "A0_7") (pintype "bidirectional"))
      (node (ref "IC5") (pin "1") (pinfunction "A0_1") (pintype "bidirectional"))
      (node (ref "IC5") (pin "2") (pinfunction "A1_2") (pintype "bidirectional"))
      (node (ref "IC5") (pin "3") (pinfunction "A2_3") (pintype "bidirectional"))
      (node (ref "IC5") (pin "4") (pinfunction "VSS_4") (pintype "power_in"))
      (node (ref "JP3") (pin "1") (pinfunction "1_1") (pintype "passive"))
      (node (ref "LCD1") (pin "K") (pinfunction "K_K") (pintype "bidirectional"))
      (node (ref "LCD1") (pin "P$11") (pinfunction "VSS_P$11") (pintype "bidirectional"))
      (node (ref "R16") (pin "2") (pinfunction "P$2_2") (pintype "passive"))
      (node (ref "R28") (pin "2") (pinfunction "P$2_2") (pintype "passive"))
      (node (ref "R3") (pin "1") (pinfunction "P$1_1") (pintype "passive"))
      (node (ref "SW1") (pin "B1") (pinfunction "B1_B1") (pintype "passive"))
      (node (ref "SW1") (pin "B2") (pinfunction "B2_B2") (pintype "passive"))
      (node (ref "T2") (pin "2") (pinfunction "E_2") (pintype "passive"))
      (node (ref "TP12") (pin "TP") (pinfunction "TP_TP") (pintype "input"))
      (node (ref "TP13") (pin "TP") (pinfunction "TP_TP") (pintype "input"))
      (node (ref "TP14") (pin "TP") (pinfunction "TP_TP") (pintype "input"))
      (node (ref "TP15") (pin "TP") (pinfunction "TP_TP") (pintype "input"))
      (node (ref "TP2") (pin "TP") (pinfunction "TP_TP") (pintype "input"))
      (node (ref "VR1") (pin "P$1") (pinfunction "A_P$1") (pintype "passive"))
    )
    (net (code "9") (name "GP0") (class "Default")
      (node (ref "R16") (pin "1") (pinfunction "P$1_1") (pintype "passive"))
      (node (ref "SKT1") (pin "16") (pinfunction "GP0_16") (pintype "bidirectional"))
      (node (ref "SKT1") (pin "P$56") (pinfunction "P$56_P$56") (pintype "bidirectional"))
      (node (ref "SW2") (pin "A1") (pinfunction "A1_A1") (pintype "passive"))
      (node (ref "SW2") (pin "A2") (pinfunction "A2_A2") (pintype "passive"))
    )
    (net (code "10") (name "GP1") (class "Default")
      (node (ref "CON1") (pin "4") (pinfunction "SEL_4") (pintype "bidirectional"))
      (node (ref "SKT1") (pin "17") (pinfunction "GP1_17") (pintype "bidirectional"))
      (node (ref "SKT1") (pin "P$57") (pinfunction "P$57_P$57") (pintype "bidirectional"))
    )
    (net (code "11") (name "GP2") (class "Default")
      (node (ref "CON10") (pin "2") (pinfunction "NCS_2") (pintype "bidirectional"))
      (node (ref "CON4") (pin "1") (pinfunction "A/D0_1") (pintype "bidirectional"))
      (node (ref "R24") (pin "2") (pinfunction "P$2_2") (pintype "passive"))
      (node (ref "SKT1") (pin "24") (pinfunction "GP2_24") (pintype "bidirectional"))
      (node (ref "SKT1") (pin "P$64") (pinfunction "P$64_P$64") (pintype "bidirectional"))
    )
    (net (code "12") (name "GP3") (class "Default")
      (node (ref "CON4") (pin "2") (pinfunction "A/D1_2") (pintype "bidirectional"))
      (node (ref "R24") (pin "1") (pinfunction "P$1_1") (pintype "passive"))
      (node (ref "SKT1") (pin "25") (pinfunction "GP3_25") (pintype "bidirectional"))
      (node (ref "SKT1") (pin "P$65") (pinfunction "P$65_P$65") (pintype "bidirectional"))
    )
    (net (code "13") (name "GP4") (class "Default")
      (node (ref "CON7") (pin "4") (pinfunction "SEL_4") (pintype "bidirectional"))
      (node (ref "SKT1") (pin "33") (pinfunction "GP4_33") (pintype "bidirectional"))
      (node (ref "SKT1") (pin "P$73") (pinfunction "P$73_P$73") (pintype "bidirectional"))
    )
    (net (code "14") (name "GP5") (class "Default")
      (node (ref "LCD1") (pin "P$15") (pinfunction "A0_P$15") (pintype "bidirectional"))
      (node (ref "SKT1") (pin "34") (pinfunction "GP5_34") (pintype "bidirectional"))
      (node (ref "SKT1") (pin "P$74") (pinfunction "P$74_P$74") (pintype "bidirectional"))
    )
    (net (code "15") (name "GP6") (class "Default")
      (node (ref "LCD1") (pin "P$16") (pinfunction "RST_P$16") (pintype "bidirectional"))
      (node (ref "SKT1") (pin "35") (pinfunction "GP6_35") (pintype "bidirectional"))
      (node (ref "SKT1") (pin "P$75") (pinfunction "P$75_P$75") (pintype "bidirectional"))
    )
    (net (code "16") (name "GP7") (class "Default")
      (node (ref "LCD1") (pin "P$17") (pinfunction "CS1B_P$17") (pintype "bidirectional"))
      (node (ref "SKT1") (pin "36") (pinfunction "GP7_36") (pintype "bidirectional"))
      (node (ref "SKT1") (pin "P$76") (pinfunction "P$76_P$76") (pintype "bidirectional"))
    )
    (net (code "17") (name "GP8") (class "Default")
      (node (ref "SKT1") (pin "37") (pinfunction "GP8_37") (pintype "bidirectional"))
      (node (ref "SKT1") (pin "P$77") (pinfunction "P$77_P$77") (pintype "bidirectional"))
    )
    (net (code "18") (name "IF_NRESET") (class "Default")
      (node (ref "C4") (pin "1") (pinfunction "P$1_1") (pintype "passive"))
      (node (ref "IC3") (pin "2") (pinfunction "~{RESET}/PIO0_0_2") (pintype "bidirectional"))
      (node (ref "R5") (pin "1") (pinfunction "P$1_1") (pintype "passive"))
    )
    (net (code "19") (name "IF_SCL") (class "Default")
      (node (ref "IC3") (pin "10") (pinfunction "PIO0_4/SCL_10") (pintype "bidirectional"))
      (node (ref "TP4") (pin "TP") (pinfunction "TP_TP") (pintype "input"))
    )
    (net (code "20") (name "IF_SDA") (class "Default")
      (node (ref "IC3") (pin "11") (pinfunction "PIO0_5/SDA_11") (pintype "bidirectional"))
      (node (ref "TP5") (pin "TP") (pinfunction "TP_TP") (pintype "input"))
    )
    (net (code "21") (name "IF_SWCLK") (class "Default")
      (node (ref "IC3") (pin "19") (pinfunction "SWCLK/PIO0_10/SCK0/CT16B0_MAT2_19") (pintype "bidirectional"))
      (node (ref "TP10") (pin "TP") (pinfunction "TP_TP") (pintype "input"))
    )
    (net (code "22") (name "IF_SWDIO") (class "Default")
      (node (ref "IC3") (pin "25") (pinfunction "SWDIO/PIO0_15/AD4/CT32B1_MAT2_25") (pintype "bidirectional"))
      (node (ref "TP9") (pin "TP") (pinfunction "TP_TP") (pintype "input"))
    )
    (net (code "23") (name "LED_COM_GREEN") (class "Default")
      (node (ref "IC3") (pin "21") (pinfunction "TDI/PIO0_11/AD0/CT32B0_MAT3_21") (pintype "bidirectional"))
      (node (ref "LED2") (pin "C") (pinfunction "C_C") (pintype "passive"))
    )
    (net (code "24") (name "LED_DAP_BLUE") (class "Default")
      (node (ref "IC3") (pin "12") (pinfunction "PIO0_21/CT16B1_MAT0_12") (pintype "bidirectional"))
      (node (ref "LED1") (pin "C") (pinfunction "C_C") (pintype "passive"))
    )
    (net (code "25") (name "LED_PWR_RED") (class "Default")
      (node (ref "IC3") (pin "7") (pinfunction "PIO0_20/CT16B1_CAP0_7") (pintype "bidirectional"))
      (node (ref "LED3") (pin "A") (pinfunction "A_A") (pintype "passive"))
    )
    (net (code "26") (name "MISO1") (class "Default")
      (node (ref "CON1") (pin "2") (pinfunction "MISO_2") (pintype "bidirectional"))
      (node (ref "CON10") (pin "7") (pinfunction "MISO_7") (pintype "bidirectional"))
      (node (ref "SKT1") (pin "14") (pinfunction "MISO1_14") (pintype "bidirectional"))
      (node (ref "SKT1") (pin "P$54") (pinfunction "P$54_P$54") (pintype "bidirectional"))
    )
    (net (code "27") (name "MISO2") (class "Default")
      (node (ref "CON7") (pin "2") (pinfunction "MISO_2") (pintype "bidirectional"))
      (node (ref "SKT1") (pin "27") (pinfunction "MISO2_27") (pintype "bidirectional"))
      (node (ref "SKT1") (pin "P$67") (pinfunction "P$67_P$67") (pintype "bidirectional"))
    )
    (net (code "28") (name "MODULE_GND") (class "Default")
      (node (ref "R28") (pin "1") (pinfunction "P$1_1") (pintype "passive"))
      (node (ref "SKT1") (pin "1") (pinfunction "GND_1") (pintype "bidirectional"))
      (node (ref "SKT1") (pin "40") (pinfunction "GND_40") (pintype "bidirectional"))
      (node (ref "SKT1") (pin "P$41") (pinfunction "P$41_P$41") (pintype "bidirectional"))
      (node (ref "SKT1") (pin "P$80") (pinfunction "P$80_P$80") (pintype "bidirectional"))
      (node (ref "T2") (pin "3") (pinfunction "C_3") (pintype "passive"))
    )
    (net (code "29") (name "MOSI1") (class "Default")
      (node (ref "CON1") (pin "3") (pinfunction "MOSI_3") (pintype "bidirectional"))
      (node (ref "CON10") (pin "3") (pinfunction "MOSI_3") (pintype "bidirectional"))
      (node (ref "LCD1") (pin "P$13") (pinfunction "SDA_P$13") (pintype "bidirectional"))
      (node (ref "SKT1") (pin "13") (pinfunction "MOSI1_13") (pintype "bidirectional"))
      (node (ref "SKT1") (pin "P$53") (pinfunction "P$53_P$53") (pintype "bidirectional"))
    )
    (net (code "30") (name "MOSI2") (class "Default")
      (node (ref "CON7") (pin "3") (pinfunction "MOSI_3") (pintype "bidirectional"))
      (node (ref "SKT1") (pin "28") (pinfunction "MOSI2_28") (pintype "bidirectional"))
      (node (ref "SKT1") (pin "P$68") (pinfunction "P$68_P$68") (pintype "bidirectional"))
    )
    (net (code "31") (name "Net-(C6-P$1)") (class "Default")
      (node (ref "C6") (pin "1") (pinfunction "P$1_1") (pintype "passive"))
      (node (ref "IC3") (pin "5") (pinfunction "XTALOUT_5") (pintype "output"))
      (node (ref "Q1") (pin "P$1") (pinfunction "1_P$1") (pintype "passive"))
    )
    (net (code "32") (name "Net-(C7-P$1)") (class "Default")
      (node (ref "C7") (pin "1") (pinfunction "P$1_1") (pintype "passive"))
      (node (ref "IC3") (pin "4") (pinfunction "XTALIN_4") (pintype "input"))
      (node (ref "Q1") (pin "P$3") (pinfunction "2_P$3") (pintype "passive"))
    )
    (net (code "33") (name "Net-(C8-P$1)") (class "Default")
      (node (ref "C8") (pin "1") (pinfunction "P$1_1") (pintype "passive"))
      (node (ref "IC3") (pin "13") (pinfunction "USB_DM_13") (pintype "bidirectional"))
      (node (ref "R9") (pin "2") (pinfunction "P$2_2") (pintype "passive"))
    )
    (net (code "34") (name "Net-(C9-P$1)") (class "Default")
      (node (ref "C9") (pin "1") (pinfunction "P$1_1") (pintype "passive"))
      (node (ref "IC3") (pin "14") (pinfunction "USB_DP_14") (pintype "bidirectional"))
      (node (ref "R10") (pin "2") (pinfunction "P$2_2") (pintype "passive"))
      (node (ref "R8") (pin "2") (pinfunction "P$2_2") (pintype "passive"))
    )
    (net (code "35") (name "Net-(C11-P$1)") (class "Default")
      (node (ref "C11") (pin "1") (pinfunction "P$1_1") (pintype "passive"))
      (node (ref "LCD1") (pin "P$1") (pinfunction "V0_P$1") (pintype "bidirectional"))
    )
    (net (code "36") (name "Net-(C12-P$1)") (class "Default")
      (node (ref "C12") (pin "1") (pinfunction "P$1_1") (pintype "passive"))
      (node (ref "LCD1") (pin "P$2") (pinfunction "V1_P$2") (pintype "bidirectional"))
    )
    (net (code "37") (name "Net-(C13-P$1)") (class "Default")
      (node (ref "C13") (pin "1") (pinfunction "P$1_1") (pintype "passive"))
      (node (ref "LCD1") (pin "P$3") (pinfunction "V2_P$3") (pintype "bidirectional"))
    )
    (net (code "38") (name "Net-(C14-P$1)") (class "Default")
      (node (ref "C14") (pin "1") (pinfunction "P$1_1") (pintype "passive"))
      (node (ref "LCD1") (pin "P$4") (pinfunction "V3_P$4") (pintype "bidirectional"))
    )
    (net (code "39") (name "Net-(C15-P$1)") (class "Default")
      (node (ref "C15") (pin "1") (pinfunction "P$1_1") (pintype "passive"))
      (node (ref "LCD1") (pin "P$5") (pinfunction "V4_P$5") (pintype "bidirectional"))
    )
    (net (code "40") (name "Net-(C16-P$1)") (class "Default")
      (node (ref "C16") (pin "1") (pinfunction "P$1_1") (pintype "passive"))
      (node (ref "LCD1") (pin "P$9") (pinfunction "C1-_P$9") (pintype "bidirectional"))
    )
    (net (code "41") (name "Net-(C16-P$2)") (class "Default")
      (node (ref "C16") (pin "2") (pinfunction "P$2_2") (pintype "passive"))
      (node (ref "LCD1") (pin "P$8") (pinfunction "C1+_P$8") (pintype "bidirectional"))
    )
    (net (code "42") (name "Net-(C17-P$1)") (class "Default")
      (node (ref "C17") (pin "1") (pinfunction "P$1_1") (pintype "passive"))
      (node (ref "LCD1") (pin "P$7") (pinfunction "C2+_P$7") (pintype "bidirectional"))
    )
    (net (code "43") (name "Net-(C17-P$2)") (class "Default")
      (node (ref "C17") (pin "2") (pinfunction "P$2_2") (pintype "passive"))
      (node (ref "LCD1") (pin "P$6") (pinfunction "C2-_P$6") (pintype "bidirectional"))
    )
    (net (code "44") (name "Net-(C18-P$1)") (class "Default")
      (node (ref "C18") (pin "1") (pinfunction "P$1_1") (pintype "passive"))
      (node (ref "LCD1") (pin "P$10") (pinfunction "VOUT_P$10") (pintype "bidirectional"))
    )
    (net (code "45") (name "Net-(CON9-PadD+)") (class "Default")
      (node (ref "CON9") (pin "D+") (pinfunction "D+_D+") (pintype "bidirectional"))
      (node (ref "IC1") (pin "1") (pinfunction "IO1_1") (pintype "bidirectional"))
    )
    (net (code "46") (name "Net-(CON9-PadD-)") (class "Default")
      (node (ref "CON9") (pin "D-") (pinfunction "D-_D-") (pintype "bidirectional"))
      (node (ref "IC1") (pin "3") (pinfunction "IO2_3") (pintype "bidirectional"))
    )
    (net (code "47") (name "Net-(CON12-PWR-Pad1-1)") (class "Default")
      (node (ref "CON12") (pin "1-1") (pinfunction "PWR_1-1") (pintype "bidirectional"))
      (node (ref "CON12") (pin "1-2") (pinfunction "PWR_1-2") (pintype "bidirectional"))
      (node (ref "D2") (pin "A") (pinfunction "A_A") (pintype "passive"))
    )
    (net (code "48") (name "Net-(IC1-VBUS)") (class "Default")
      (node (ref "CON9") (pin "VBUS") (pinfunction "VBUS_VBUS") (pintype "bidirectional"))
      (node (ref "D3") (pin "A") (pinfunction "A_A") (pintype "passive"))
      (node (ref "IC1") (pin "5") (pinfunction "VBUS_5") (pintype "bidirectional"))
    )
    (net (code "49") (name "Net-(IC2-IN)") (class "Default")
      (node (ref "IC2") (pin "3") (pinfunction "IN_3") (pintype "input"))
      (node (ref "SW3") (pin "3") (pinfunction "3_3") (pintype "bidirectional"))
    )
    (net (code "50") (name "Net-(IC3-PIO0_3{slash}USB_VBUS)") (class "Default")
      (node (ref "IC3") (pin "9") (pinfunction "PIO0_3/USB_VBUS_9") (pintype "bidirectional"))
      (node (ref "R4") (pin "1") (pinfunction "P$1_1") (pintype "passive"))
    )
    (net (code "51") (name "Net-(R1-P$2)") (class "Default")
      (node (ref "LED1") (pin "A") (pinfunction "A_A") (pintype "passive"))
      (node (ref "R1") (pin "2") (pinfunction "P$2_2") (pintype "passive"))
    )
    (net (code "52") (name "Net-(R2-P$2)") (class "Default")
      (node (ref "LED2") (pin "A") (pinfunction "A_A") (pintype "passive"))
      (node (ref "R2") (pin "2") (pinfunction "P$2_2") (pintype "passive"))
    )
    (net (code "53") (name "Net-(R3-P$2)") (class "Default")
      (node (ref "LED3") (pin "C") (pinfunction "C_C") (pintype "passive"))
      (node (ref "R3") (pin "2") (pinfunction "P$2_2") (pintype "passive"))
    )
    (net (code "54") (name "Net-(R8-P$1)") (class "Default")
      (node (ref "R8") (pin "1") (pinfunction "P$1_1") (pintype "passive"))
      (node (ref "T1") (pin "3") (pinfunction "D_3") (pintype "passive"))
    )
    (net (code "55") (name "Net-(R11-P$2)") (class "Default")
      (node (ref "LED4") (pin "C") (pinfunction "C_C") (pintype "passive"))
      (node (ref "R11") (pin "2") (pinfunction "P$2_2") (pintype "passive"))
    )
    (net (code "56") (name "Net-(R12-P$2)") (class "Default")
      (node (ref "LED5") (pin "C") (pinfunction "C_C") (pintype "passive"))
      (node (ref "R12") (pin "2") (pinfunction "P$2_2") (pintype "passive"))
    )
    (net (code "57") (name "Net-(R13-P$2)") (class "Default")
      (node (ref "LED6") (pin "C") (pinfunction "C_C") (pintype "passive"))
      (node (ref "R13") (pin "2") (pinfunction "P$2_2") (pintype "passive"))
    )
    (net (code "58") (name "Net-(R17-P$2)") (class "Default")
      (node (ref "LCD1") (pin "A") (pinfunction "A_A") (pintype "bidirectional"))
      (node (ref "R17") (pin "2") (pinfunction "P$2_2") (pintype "passive"))
    )
    (net (code "59") (name "Net-(R19-P$2)") (class "Default")
      (node (ref "R19") (pin "2") (pinfunction "P$2_2") (pintype "passive"))
      (node (ref "R20") (pin "2") (pinfunction "P$2_2") (pintype "passive"))
      (node (ref "R21") (pin "2") (pinfunction "P$2_2") (pintype "passive"))
      (node (ref "TP3") (pin "TP") (pinfunction "TP_TP") (pintype "input"))
    )
    (net (code "60") (name "Net-(R22-P$1)") (class "Default")
      (node (ref "R22") (pin "1") (pinfunction "P$1_1") (pintype "passive"))
      (node (ref "VR1") (pin "P$2") (pinfunction "S_P$2") (pintype "passive"))
    )
    (net (code "61") (name "Net-(R26-P$1)") (class "Default")
      (node (ref "R26") (pin "1") (pinfunction "P$1_1") (pintype "passive"))
      (node (ref "T2") (pin "1") (pinfunction "B_1") (pintype "passive"))
    )
    (net (code "62") (name "Net-(R29-P$2)") (class "Default")
      (node (ref "JP3") (pin "2") (pinfunction "2_2") (pintype "passive"))
      (node (ref "R29") (pin "2") (pinfunction "P$2_2") (pintype "passive"))
      (node (ref "T3") (pin "B") (pinfunction "G_B") (pintype "passive"))
    )
    (net (code "63") (name "Net-(R30-P$2)") (class "Default")
      (node (ref "R30") (pin "2") (pinfunction "P$2_2") (pintype "passive"))
      (node (ref "SW3") (pin "2") (pinfunction "2_2") (pintype "bidirectional"))
      (node (ref "T3") (pin "C") (pinfunction "D_C") (pintype "passive"))
    )
    (net (code "64") (name "PIO0_14") (class "Default")
      (node (ref "IC3") (pin "24") (pinfunction "~{TRST}/PIO0_14/AD3/CT32B1_MAT1_24") (pintype "bidirectional"))
      (node (ref "TP11") (pin "TP") (pinfunction "TP_TP") (pintype "input"))
    )
    (net (code "65") (name "PWM0-RED") (class "Default")
      (node (ref "R11") (pin "1") (pinfunction "P$1_1") (pintype "passive"))
      (node (ref "SKT1") (pin "21") (pinfunction "PWM0_21") (pintype "bidirectional"))
      (node (ref "SKT1") (pin "P$61") (pinfunction "P$61_P$61") (pintype "bidirectional"))
    )
    (net (code "66") (name "PWM1-BLUE") (class "Default")
      (node (ref "R12") (pin "1") (pinfunction "P$1_1") (pintype "passive"))
      (node (ref "SKT1") (pin "22") (pinfunction "PWM1_22") (pintype "bidirectional"))
      (node (ref "SKT1") (pin "P$62") (pinfunction "P$62_P$62") (pintype "bidirectional"))
    )
    (net (code "67") (name "PWM2-GREEN") (class "Default")
      (node (ref "R13") (pin "1") (pinfunction "P$1_1") (pintype "passive"))
      (node (ref "SKT1") (pin "23") (pinfunction "PWM2_23") (pintype "bidirectional"))
      (node (ref "SKT1") (pin "P$63") (pinfunction "P$63_P$63") (pintype "bidirectional"))
    )
    (net (code "68") (name "RX1") (class "Default")
      (node (ref "CON2") (pin "1") (pinfunction "RX/SCL_1") (pintype "bidirectional"))
      (node (ref "R23") (pin "2") (pinfunction "P$2_2") (pintype "passive"))
      (node (ref "SKT1") (pin "10") (pinfunction "RX1_10") (pintype "bidirectional"))
      (node (ref "SKT1") (pin "P$50") (pinfunction "P$50_P$50") (pintype "bidirectional"))
    )
    (net (code "69") (name "RX2") (class "Default")
      (node (ref "CON6") (pin "1") (pinfunction "RX/SCL_1") (pintype "bidirectional"))
      (node (ref "R18") (pin "2") (pinfunction "P$2_2") (pintype "passive"))
      (node (ref "SKT1") (pin "31") (pinfunction "RX2_31") (pintype "bidirectional"))
      (node (ref "SKT1") (pin "P$71") (pinfunction "P$71_P$71") (pintype "bidirectional"))
    )
    (net (code "70") (name "SCK1") (class "Default")
      (node (ref "CON1") (pin "1") (pinfunction "SCK_1") (pintype "bidirectional"))
      (node (ref "CON10") (pin "5") (pinfunction "SCK_5") (pintype "bidirectional"))
      (node (ref "LCD1") (pin "P$14") (pinfunction "SCL_P$14") (pintype "bidirectional"))
      (node (ref "SKT1") (pin "15") (pinfunction "SCK1_15") (pintype "bidirectional"))
      (node (ref "SKT1") (pin "P$55") (pinfunction "P$55_P$55") (pintype "bidirectional"))
    )
    (net (code "71") (name "SCK2") (class "Default")
      (node (ref "CON7") (pin "1") (pinfunction "SCK_1") (pintype "bidirectional"))
      (node (ref "SKT1") (pin "26") (pinfunction "SCK2_26") (pintype "bidirectional"))
      (node (ref "SKT1") (pin "P$66") (pinfunction "P$66_P$66") (pintype "bidirectional"))
    )
    (net (code "72") (name "SCL") (class "Default")
      (node (ref "IC4") (pin "2") (pinfunction "SCL_2") (pintype "bidirectional"))
      (node (ref "IC5") (pin "6") (pinfunction "SCL_6") (pintype "bidirectional"))
      (node (ref "JP4") (pin "4") (pinfunction "4_4") (pintype "passive"))
      (node (ref "R15") (pin "1") (pinfunction "P$1_1") (pintype "passive"))
    )
    (net (code "73") (name "SCL1") (class "Default")
      (node (ref "CON5") (pin "1") (pinfunction "RX/SCL_1") (pintype "bidirectional"))
      (node (ref "JP4") (pin "2") (pinfunction "2_2") (pintype "passive"))
      (node (ref "SKT1") (pin "12") (pinfunction "SCL1_12") (pintype "bidirectional"))
      (node (ref "SKT1") (pin "P$52") (pinfunction "P$52_P$52") (pintype "bidirectional"))
    )
    (net (code "74") (name "SCL2") (class "Default")
      (node (ref "CON8") (pin "1") (pinfunction "RX/SCL_1") (pintype "bidirectional"))
      (node (ref "JP4") (pin "6") (pinfunction "6_6") (pintype "passive"))
      (node (ref "SKT1") (pin "29") (pinfunction "SCL2_29") (pintype "bidirectional"))
      (node (ref "SKT1") (pin "P$69") (pinfunction "P$69_P$69") (pintype "bidirectional"))
    )
    (net (code "75") (name "SDA") (class "Default")
      (node (ref "IC4") (pin "1") (pinfunction "SDA_1") (pintype "bidirectional"))
      (node (ref "IC5") (pin "5") (pinfunction "SDA_5") (pintype "bidirectional"))
      (node (ref "JP4") (pin "3") (pinfunction "3_3") (pintype "passive"))
      (node (ref "R14") (pin "1") (pinfunction "P$1_1") (pintype "passive"))
    )
    (net (code "76") (name "SDA1") (class "Default")
      (node (ref "CON5") (pin "2") (pinfunction "TX/SDA_2") (pintype "bidirectional"))
      (node (ref "JP4") (pin "1") (pinfunction "1_1") (pintype "passive"))
      (node (ref "SKT1") (pin "11") (pinfunction "SDA1_11") (pintype "bidirectional"))
      (node (ref "SKT1") (pin "P$51") (pinfunction "P$51_P$51") (pintype "bidirectional"))
    )
    (net (code "77") (name "SDA2") (class "Default")
      (node (ref "CON8") (pin "2") (pinfunction "TX/SDA_2") (pintype "bidirectional"))
      (node (ref "JP4") (pin "5") (pinfunction "5_5") (pintype "passive"))
      (node (ref "SKT1") (pin "30") (pinfunction "SDA2_30") (pintype "bidirectional"))
      (node (ref "SKT1") (pin "P$70") (pinfunction "P$70_P$70") (pintype "bidirectional"))
    )
    (net (code "78") (name "TGT_CTS") (class "Default")
      (node (ref "IC3") (pin "30") (pinfunction "PIO0_17/~{RTS}/CT32B0_CAP0/SCLK_30") (pintype "bidirectional"))
      (node (ref "SKT1") (pin "39") (pinfunction "TGT_CTS_39") (pintype "bidirectional"))
      (node (ref "SKT1") (pin "P$79") (pinfunction "P$79_P$79") (pintype "bidirectional"))
    )
    (net (code "79") (name "TGT_NRESET") (class "Default")
      (node (ref "CON11") (pin "10") (pinfunction "NRESET_10") (pintype "bidirectional"))
      (node (ref "D1") (pin "A") (pinfunction "A_A") (pintype "passive"))
      (node (ref "IC3") (pin "8") (pinfunction "PIO0_2/SSEL0/CT16B0_CAP0_8") (pintype "bidirectional"))
      (node (ref "SKT1") (pin "6") (pinfunction "NRESET_6") (pintype "bidirectional"))
      (node (ref "SKT1") (pin "P$46") (pinfunction "P$46_P$46") (pintype "bidirectional"))
    )
    (net (code "80") (name "TGT_NRESET_BUTTON") (class "Default")
      (node (ref "D1") (pin "K") (pinfunction "K_K") (pintype "passive"))
      (node (ref "R6") (pin "2") (pinfunction "P$2_2") (pintype "passive"))
      (node (ref "R7") (pin "2") (pinfunction "P$2_2") (pintype "passive"))
      (node (ref "SW1") (pin "A1") (pinfunction "A1_A1") (pintype "passive"))
      (node (ref "SW1") (pin "A2") (pinfunction "A2_A2") (pintype "passive"))
    )
    (net (code "81") (name "TGT_NRESET_FB") (class "Default")
      (node (ref "IC3") (pin "3") (pinfunction "PIO0_1/CLKOUT/CT32B0_MAT2/USB_FTOGGLE_3") (pintype "bidirectional"))
      (node (ref "R6") (pin "1") (pinfunction "P$1_1") (pintype "passive"))
    )
    (net (code "82") (name "TGT_NRESET_FB_ISP") (class "Default")
      (node (ref "IC3") (pin "1") (pinfunction "PIO1_19/~{DTR}/SSEL1_1") (pintype "bidirectional"))
      (node (ref "R7") (pin "1") (pinfunction "P$1_1") (pintype "passive"))
    )
    (net (code "83") (name "TGT_RTS") (class "Default")
      (node (ref "IC3") (pin "16") (pinfunction "PIO0_7/~{CTS}_16") (pintype "bidirectional"))
      (node (ref "JP2") (pin "2") (pinfunction "2_2") (pintype "passive"))
      (node (ref "SKT1") (pin "38") (pinfunction "TGT_RTS_38") (pintype "bidirectional"))
      (node (ref "SKT1") (pin "P$78") (pinfunction "P$78_P$78") (pintype "bidirectional"))
    )
    (net (code "84") (name "TGT_RX") (class "Default")
      (node (ref "CON11") (pin "8") (pinfunction "TGT_RX_8") (pintype "bidirectional"))
      (node (ref "IC3") (pin "32") (pinfunction "PIO0_19/TXD/CT32B0_MAT1_32") (pintype "bidirectional"))
      (node (ref "SKT1") (pin "8") (pinfunction "TGT_RX_8") (pintype "bidirectional"))
      (node (ref "SKT1") (pin "P$48") (pinfunction "P$48_P$48") (pintype "bidirectional"))
    )
    (net (code "85") (name "TGT_SWCLK") (class "Default")
      (node (ref "CON11") (pin "4") (pinfunction "SWCLK_4") (pintype "bidirectional"))
      (node (ref "IC3") (pin "18") (pinfunction "PIO0_9/MOSI0/CT16B0_MAT1_18") (pintype "bidirectional"))
      (node (ref "JP2") (pin "1") (pinfunction "1_1") (pintype "passive"))
      (node (ref "SKT1") (pin "5") (pinfunction "SWCLK_5") (pintype "bidirectional"))
      (node (ref "SKT1") (pin "P$45") (pinfunction "P$45_P$45") (pintype "bidirectional"))
    )
    (net (code "86") (name "TGT_SWDIO") (class "Default")
      (node (ref "CON11") (pin "2") (pinfunction "SWDIO_2") (pintype "bidirectional"))
      (node (ref "IC3") (pin "17") (pinfunction "PIO0_8/MISO0/CT16B0_MAT0_17") (pintype "bidirectional"))
      (node (ref "SKT1") (pin "4") (pinfunction "SWDIO_4") (pintype "bidirectional"))
      (node (ref "SKT1") (pin "P$44") (pinfunction "P$44_P$44") (pintype "bidirectional"))
    )
    (net (code "87") (name "TGT_TX") (class "Default")
      (node (ref "CON11") (pin "7") (pinfunction "TGT_TX_7") (pintype "bidirectional"))
      (node (ref "IC3") (pin "31") (pinfunction "PIO0_18/RXD/CT32B0_MAT0_31") (pintype "bidirectional"))
      (node (ref "SKT1") (pin "7") (pinfunction "TGT_TX_7") (pintype "bidirectional"))
      (node (ref "SKT1") (pin "P$47") (pinfunction "P$47_P$47") (pintype "bidirectional"))
    )
    (net (code "88") (name "TX1") (class "Default")
      (node (ref "CON2") (pin "2") (pinfunction "TX/SDA_2") (pintype "bidirectional"))
      (node (ref "R23") (pin "1") (pinfunction "P$1_1") (pintype "passive"))
      (node (ref "SKT1") (pin "9") (pinfunction "TX1_9") (pintype "bidirectional"))
      (node (ref "SKT1") (pin "P$49") (pinfunction "P$49_P$49") (pintype "bidirectional"))
    )
    (net (code "89") (name "TX2") (class "Default")
      (node (ref "CON6") (pin "2") (pinfunction "TX/SDA_2") (pintype "bidirectional"))
      (node (ref "R18") (pin "1") (pinfunction "P$1_1") (pintype "passive"))
      (node (ref "SKT1") (pin "32") (pinfunction "TX2_32") (pintype "bidirectional"))
      (node (ref "SKT1") (pin "P$72") (pinfunction "P$72_P$72") (pintype "bidirectional"))
    )
    (net (code "90") (name "USB-D+") (class "Default")
      (node (ref "IC1") (pin "6") (pinfunction "IO1_6") (pintype "bidirectional"))
      (node (ref "R10") (pin "1") (pinfunction "P$1_1") (pintype "passive"))
    )
    (net (code "91") (name "USB-D-") (class "Default")
      (node (ref "IC1") (pin "4") (pinfunction "IO2_4") (pintype "bidirectional"))
      (node (ref "R9") (pin "1") (pinfunction "P$1_1") (pintype "passive"))
    )
    (net (code "92") (name "USB-SCON") (class "Default")
      (node (ref "IC3") (pin "15") (pinfunction "PIO0_6/~{USB_CONNECT}/SCK0_15") (pintype "bidirectional"))
      (node (ref "T1") (pin "1") (pinfunction "G_1") (pintype "passive"))
    )
    (net (code "93") (name "VCC_GROVE") (class "Default")
      (node (ref "CON2") (pin "3") (pinfunction "VCC_3") (pintype "bidirectional"))
      (node (ref "CON3") (pin "3") (pinfunction "VCC_3") (pintype "bidirectional"))
      (node (ref "CON4") (pin "3") (pinfunction "VCC_3") (pintype "bidirectional"))
      (node (ref "CON5") (pin "3") (pinfunction "VCC_3") (pintype "bidirectional"))
      (node (ref "CON6") (pin "3") (pinfunction "VCC_3") (pintype "bidirectional"))
      (node (ref "CON8") (pin "3") (pinfunction "VCC_3") (pintype "bidirectional"))
      (node (ref "JP1") (pin "2") (pinfunction "2_2") (pintype "passive"))
    )
    (net (code "94") (name "V_ISENSE") (class "Default")
      (node (ref "CON11") (pin "1") (pinfunction "VCC_1") (pintype "bidirectional"))
      (node (ref "R25") (pin "1") (pinfunction "P$1_1") (pintype "passive"))
      (node (ref "SKT1") (pin "2") (pinfunction "3V3_2") (pintype "bidirectional"))
      (node (ref "SKT1") (pin "P$42") (pinfunction "P$42_P$42") (pintype "bidirectional"))
      (node (ref "TP8") (pin "TP") (pinfunction "TP_TP") (pintype "input"))
    )
    (net (code "95") (name "unconnected-(CON10-NC-Pad1)") (class "Default")
      (node (ref "CON10") (pin "1") (pinfunction "NC_1") (pintype "bidirectional"))
    )
    (net (code "96") (name "unconnected-(CON10-NC-Pad8)") (class "Default")
      (node (ref "CON10") (pin "8") (pinfunction "NC_8") (pintype "bidirectional"))
    )
    (net (code "97") (name "unconnected-(CON10-PadCD)") (class "Default")
      (node (ref "CON10") (pin "CD") (pinfunction "CD_CD") (pintype "bidirectional"))
    )
    (net (code "98") (name "unconnected-(CON11-SWO-Pad6)") (class "Default")
      (node (ref "CON11") (pin "6") (pinfunction "SWO_6") (pintype "bidirectional"))
    )
    (net (code "99") (name "unconnected-(CON12-GNDBREAK-Pad2)") (class "Default")
      (node (ref "CON12") (pin "2") (pinfunction "GNDBREAK_2") (pintype "bidirectional"))
    )
    (net (code "100") (name "unconnected-(IC3-PIO0_16{slash}AD5{slash}CT32B1_MAT3{slash}WAKEUP-Pad26)") (class "Default")
      (node (ref "IC3") (pin "26") (pinfunction "PIO0_16/AD5/CT32B1_MAT3/WAKEUP_26") (pintype "bidirectional"))
    )
    (net (code "101") (name "unconnected-(IC3-PIO1_15{slash}~{DCD}{slash}CT16B0_MAT2{slash}SCK1-Pad28)") (class "Default")
      (node (ref "IC3") (pin "28") (pinfunction "PIO1_15/~{DCD}/CT16B0_MAT2/SCK1_28") (pintype "bidirectional"))
    )
    (net (code "102") (name "unconnected-(IC3-TMS{slash}PIO0_12{slash}AD1{slash}CT32B1_CAP0-Pad22)") (class "Default")
      (node (ref "IC3") (pin "22") (pinfunction "TMS/PIO0_12/AD1/CT32B1_CAP0_22") (pintype "bidirectional"))
    )
    (net (code "103") (name "unconnected-(IC4-OS-Pad3)") (class "Default")
      (node (ref "IC4") (pin "3") (pinfunction "OS_3") (pintype "bidirectional"))
    )
    (net (code "104") (name "unconnected-(IC5-WP-Pad7)") (class "Default")
      (node (ref "IC5") (pin "7") (pinfunction "WP_7") (pintype "bidirectional"))
    )
    (net (code "105") (name "unconnected-(SW3-Pad1)") (class "Default")
      (node (ref "SW3") (pin "1") (pinfunction "1_1") (pintype "bidirectional"))
    )
    (net (code "106") (name "unconnected-(SW3-Pad5)") (class "Default")
      (node (ref "SW3") (pin "5") (pinfunction "5_5") (pintype "bidirectional"))
    )
    (net (code "107") (name "unconnected-(SW3-Pad6)") (class "Default")
      (node (ref "SW3") (pin "6") (pinfunction "6_6") (pintype "bidirectional"))
    )
    (net (code "108") (name "unconnected-(SW3-Pad7)") (class "Default")
      (node (ref "SW3") (pin "7") (pinfunction "7_7") (pintype "bidirectional"))
    )
    (net (code "109") (name "~{PWR_OFF}") (class "Default")
      (node (ref "IC3") (pin "23") (pinfunction "TDO/PIO0_13/AD2/CT32B1_MAT0_23") (pintype "bidirectional"))
      (node (ref "R26") (pin "2") (pinfunction "P$2_2") (pintype "passive"))
      (node (ref "R27") (pin "2") (pinfunction "P$2_2") (pintype "passive"))
    )
  )
)
